# Nintendo_DSi_USB-C.net
KiCad netlist of a schematic drawn in EAGLE
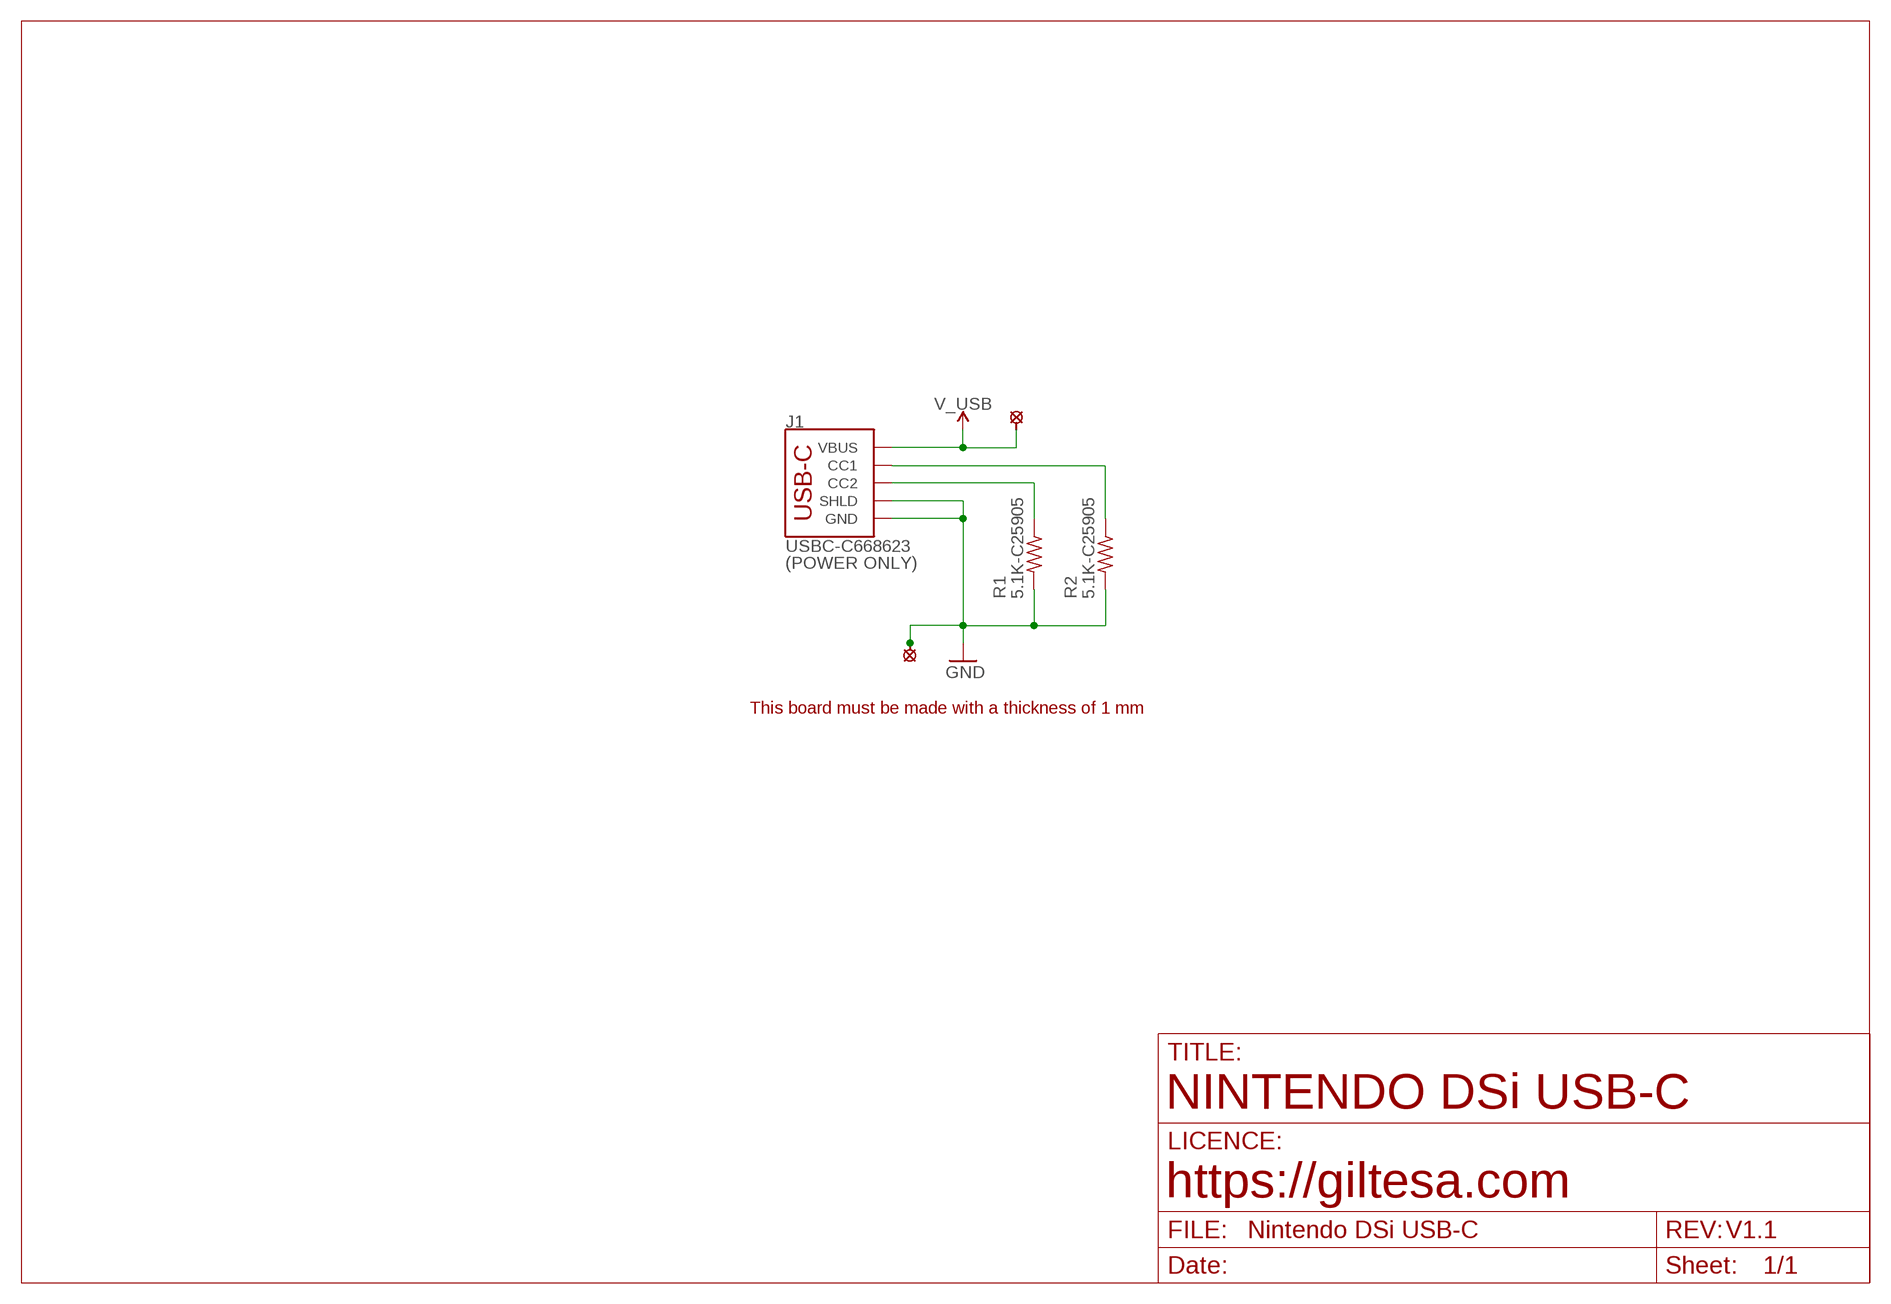
[diagram p0: schematic, sheet 1]

(export (version "E")
  (design (tool "Eeschema 10.0.6"))
  (components
    (comp (ref "J1")
      (value "USBC-C668623")
      (footprint "eagle-import:USB-C_6P")
      (libsource (lib "eagle-import") (part "USB-C_6P_POWER"))
    )
    (comp (ref "R1")
      (value "5.1K-C25905")
      (footprint "eagle-import:R0402")
      (libsource (lib "eagle-import") (part "R0402"))
    )
    (comp (ref "R2")
      (value "5.1K-C25905")
      (footprint "eagle-import:R0402")
      (libsource (lib "eagle-import") (part "R0402"))
    )
    (comp (ref "U$2")
      (value "PAD_1.0H")
      (footprint "eagle-import:PAD_1.0_HALF_MASK")
      (libsource (lib "eagle-import") (part "PAD_1.0H"))
    )
    (comp (ref "U$3")
      (value "PAD_1.0H")
      (footprint "eagle-import:PAD_1.0_HALF_MASK")
      (libsource (lib "eagle-import") (part "PAD_1.0H"))
    )
    (comp (ref "U$4")
      (value "PAD_1.0H")
      (footprint "eagle-import:PAD_1.0_HALF_MASK")
      (libsource (lib "eagle-import") (part "PAD_1.0H"))
    )
    (comp (ref "U$5")
      (value "PAD_1.0H")
      (footprint "eagle-import:PAD_1.0_HALF_MASK")
      (libsource (lib "eagle-import") (part "PAD_1.0H"))
    )
  )
  (nets
    (net (code "1") (name "GND") (class "Default")
      (node (ref "J1") (pin "A12-GND") (pinfunction "GND_A12-GND") (pintype "bidirectional"))
      (node (ref "J1") (pin "B12-GND") (pinfunction "GND_B12-GND") (pintype "bidirectional"))
      (node (ref "J1") (pin "SHLD1") (pinfunction "SHLD_SHLD1") (pintype "bidirectional"))
      (node (ref "J1") (pin "SHLD2") (pinfunction "SHLD_SHLD2") (pintype "bidirectional"))
      (node (ref "J1") (pin "SHLD3") (pinfunction "SHLD_SHLD3") (pintype "bidirectional"))
      (node (ref "J1") (pin "SHLD4") (pinfunction "SHLD_SHLD4") (pintype "bidirectional"))
      (node (ref "R1") (pin "2") (pinfunction "2_2") (pintype "passive"))
      (node (ref "R2") (pin "2") (pinfunction "2_2") (pintype "passive"))
      (node (ref "U$3") (pin "P$1") (pinfunction "P$1_P$1") (pintype "bidirectional"))
      (node (ref "U$4") (pin "P$1") (pinfunction "P$1_P$1") (pintype "bidirectional"))
      (node (ref "U$5") (pin "P$1") (pinfunction "P$1_P$1") (pintype "bidirectional"))
    )
    (net (code "2") (name "Net-(J1-CC1)") (class "Default")
      (node (ref "J1") (pin "A5") (pinfunction "CC1_A5") (pintype "bidirectional"))
      (node (ref "R2") (pin "1") (pinfunction "1_1") (pintype "passive"))
    )
    (net (code "3") (name "Net-(J1-CC2)") (class "Default")
      (node (ref "J1") (pin "B5") (pinfunction "CC2_B5") (pintype "bidirectional"))
      (node (ref "R1") (pin "1") (pinfunction "1_1") (pintype "passive"))
    )
    (net (code "4") (name "V_USB") (class "Default")
      (node (ref "J1") (pin "A9-VBUS") (pinfunction "VBUS_A9-VBUS") (pintype "bidirectional"))
      (node (ref "J1") (pin "B9-VBUS") (pinfunction "VBUS_B9-VBUS") (pintype "bidirectional"))
      (node (ref "U$2") (pin "P$1") (pinfunction "P$1_P$1") (pintype "bidirectional"))
    )
  )
)
